# Clock_Distribution.net
KiCad netlist of a schematic drawn in Altium Designer
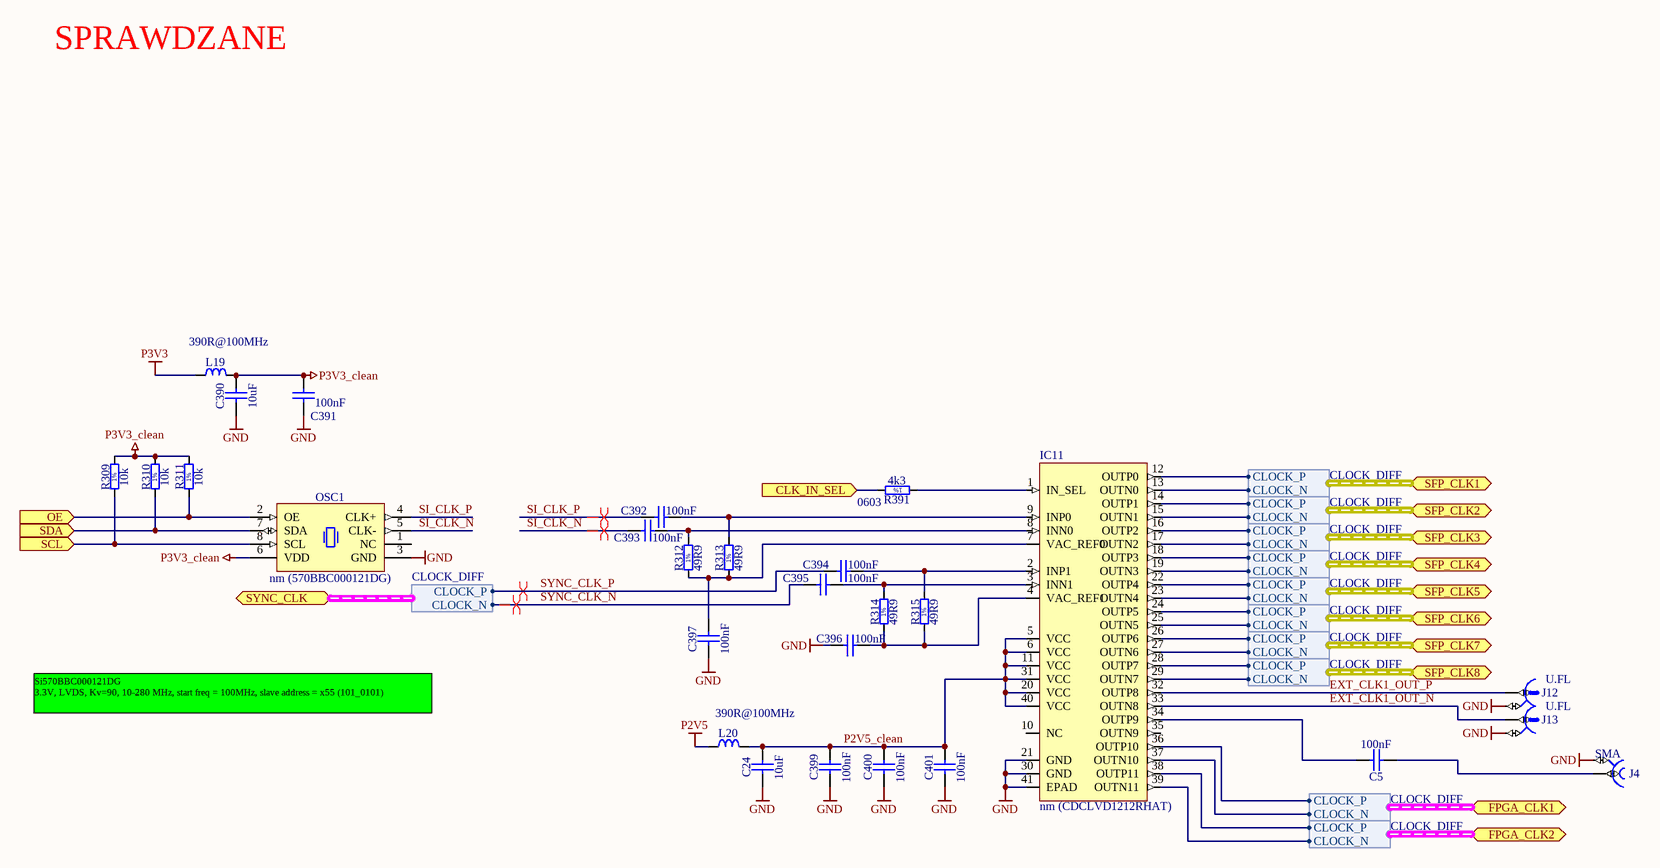
[diagram p0: Clock_Distribution.SchDoc]

(export (version "E")
  (design (tool "Eeschema 10.0.6"))
  (components
    (comp (ref "C5")
      (value "100nF")
      (footprint "CAPC1005X55N")
      (description "Non-polarised capacitor")
      (fields
        (field (name "PART NUMBER") "CC0402_100NF_16V_10%_X7R")
        (field (name "VOLTAGE") "16V")
        (field (name "AUTHOR") "CERN DEM JLC")
      )
      (libsource (lib "Capacitors") (part "Capacitor - non polarized"))
    )
    (comp (ref "C24")
      (value "10uF")
      (footprint "CAPC2012X135N")
      (description "Non-polarised capacitor")
      (fields
        (field (name "PART NUMBER") "CC0805_10UF_10V_10%_X7R")
        (field (name "VOLTAGE") "10V")
        (field (name "AUTHOR") "CERN DEM JLC")
      )
      (libsource (lib "Capacitors") (part "Capacitor - non polarized"))
    )
    (comp (ref "C390")
      (value "10uF")
      (footprint "CAPC2012X135N")
      (description "Non-polarised capacitor")
      (fields
        (field (name "PART NUMBER") "CC0805_10UF_10V_10%_X7R")
        (field (name "VOLTAGE") "10V")
        (field (name "AUTHOR") "CERN DEM JLC")
      )
      (libsource (lib "Capacitors") (part "Capacitor - non polarized"))
    )
    (comp (ref "C391")
      (value "100nF")
      (footprint "CAPC0603X33N")
      (description "Non-polarised capacitor")
      (fields
        (field (name "PART NUMBER") "CC0201_100NF_6.3V_10%_X5R")
        (field (name "VOLTAGE") "6.3V")
        (field (name "AUTHOR") "CERN DEM JLC")
      )
      (libsource (lib "Capacitors") (part "Capacitor - non polarized"))
    )
    (comp (ref "C392")
      (value "100nF")
      (footprint "CAPC0603X33N")
      (description "Non-polarised capacitor")
      (fields
        (field (name "PART NUMBER") "CC0201_100NF_6.3V_10%_X5R")
        (field (name "VOLTAGE") "6.3V")
        (field (name "AUTHOR") "CERN DEM JLC")
      )
      (libsource (lib "Capacitors") (part "Capacitor - non polarized"))
    )
    (comp (ref "C393")
      (value "100nF")
      (footprint "CAPC0603X33N")
      (description "Non-polarised capacitor")
      (fields
        (field (name "PART NUMBER") "CC0201_100NF_6.3V_10%_X5R")
        (field (name "VOLTAGE") "6.3V")
        (field (name "AUTHOR") "CERN DEM JLC")
      )
      (libsource (lib "Capacitors") (part "Capacitor - non polarized"))
    )
    (comp (ref "C394")
      (value "100nF")
      (footprint "CAPC0603X33N")
      (description "Non-polarised capacitor")
      (fields
        (field (name "PART NUMBER") "CC0201_100NF_6.3V_10%_X5R")
        (field (name "VOLTAGE") "6.3V")
        (field (name "AUTHOR") "CERN DEM JLC")
      )
      (libsource (lib "Capacitors") (part "Capacitor - non polarized"))
    )
    (comp (ref "C395")
      (value "100nF")
      (footprint "CAPC0603X33N")
      (description "Non-polarised capacitor")
      (fields
        (field (name "PART NUMBER") "CC0201_100NF_6.3V_10%_X5R")
        (field (name "VOLTAGE") "6.3V")
        (field (name "AUTHOR") "CERN DEM JLC")
      )
      (libsource (lib "Capacitors") (part "Capacitor - non polarized"))
    )
    (comp (ref "C396")
      (value "100nF")
      (footprint "CAPC0603X33N")
      (description "Non-polarised capacitor")
      (fields
        (field (name "PART NUMBER") "CC0201_100NF_6.3V_10%_X5R")
        (field (name "VOLTAGE") "6.3V")
        (field (name "AUTHOR") "CERN DEM JLC")
      )
      (libsource (lib "Capacitors") (part "Capacitor - non polarized"))
    )
    (comp (ref "C397")
      (value "100nF")
      (footprint "CAPC0603X33N")
      (description "Non-polarised capacitor")
      (fields
        (field (name "PART NUMBER") "CC0201_100NF_6.3V_10%_X5R")
        (field (name "VOLTAGE") "6.3V")
        (field (name "AUTHOR") "CERN DEM JLC")
      )
      (libsource (lib "Capacitors") (part "Capacitor - non polarized"))
    )
    (comp (ref "C399")
      (value "100nF")
      (footprint "CAPC0603X33N")
      (description "Non-polarised capacitor")
      (fields
        (field (name "PART NUMBER") "CC0201_100NF_6.3V_10%_X5R")
        (field (name "VOLTAGE") "6.3V")
        (field (name "AUTHOR") "CERN DEM JLC")
      )
      (libsource (lib "Capacitors") (part "Capacitor - non polarized"))
    )
    (comp (ref "C400")
      (value "100nF")
      (footprint "CAPC0603X33N")
      (description "Non-polarised capacitor")
      (fields
        (field (name "PART NUMBER") "CC0201_100NF_6.3V_10%_X5R")
        (field (name "VOLTAGE") "6.3V")
        (field (name "AUTHOR") "CERN DEM JLC")
      )
      (libsource (lib "Capacitors") (part "Capacitor - non polarized"))
    )
    (comp (ref "C401")
      (value "100nF")
      (footprint "CAPC0603X33N")
      (description "Non-polarised capacitor")
      (fields
        (field (name "PART NUMBER") "CC0201_100NF_6.3V_10%_X5R")
        (field (name "VOLTAGE") "6.3V")
        (field (name "AUTHOR") "CERN DEM JLC")
      )
      (libsource (lib "Capacitors") (part "Capacitor - non polarized"))
    )
    (comp (ref "IC11")
      (value "nm (CDCLVD1212RHAT)")
      (footprint "QFN50P600-40")
      (description "Low Jitter, 2-Input Selectable 1:12 Universal-to-LVDS Buffer")
      (libsource (lib "LIBRARY_SCH") (part "CLOCK_CDCLVD1212"))
    )
    (comp (ref "J4")
      (value "SMA")
      (footprint "HUBER-SUHNER_85 SMA-50-0-101/111 NE")
      (fields
        (field (name "PART NUMBER") "HUBER-SUHNER_85_SMA-50-0-101/111_NE")
        (field (name "MANUFACTURER") "HUBER+SUHNER")
        (field (name "MANUFACTURER PART NUMBER") "85_SMA-50-0-101/111_NE")
        (field (name "AUTHOR") "CERN DEM JLC")
      )
      (libsource (lib "Connectors") (part "Coax_1Female_1Shield"))
    )
    (comp (ref "J12")
      (value "U.FL")
      (footprint "HIROSE_U.FL-R-SMT-1(10)")
      (fields
        (field (name "PART NUMBER") "HIROSE_U.FL-R-SMT-1(10)")
        (field (name "MANUFACTURER") "HIROSE (HRS)")
        (field (name "MANUFACTURER PART NUMBER") "U.FL-R-SMT-1(10)")
        (field (name "AUTHOR") "CERN DEM JLC")
      )
      (libsource (lib "Connectors") (part "Coax_1Male_1Shield"))
    )
    (comp (ref "J13")
      (value "U.FL")
      (footprint "HIROSE_U.FL-R-SMT-1(10)")
      (fields
        (field (name "PART NUMBER") "HIROSE_U.FL-R-SMT-1(10)")
        (field (name "MANUFACTURER") "HIROSE (HRS)")
        (field (name "MANUFACTURER PART NUMBER") "U.FL-R-SMT-1(10)")
        (field (name "AUTHOR") "CERN DEM JLC")
      )
      (libsource (lib "Connectors") (part "Coax_1Male_1Shield"))
    )
    (comp (ref "L19")
      (value "390R@100MHz")
      (footprint "INDC1608X95N")
      (description "Inductor")
      (fields
        (field (name "PART NUMBER") "IND0603_TDK_MPZ1608R391A")
        (field (name "POWER") "1.2A")
        (field (name "AUTHOR") "CERN DEM JLC")
      )
      (libsource (lib "Inductors & Transformers") (part "Inductor"))
    )
    (comp (ref "L20")
      (value "390R@100MHz")
      (footprint "INDC1608X95N")
      (description "Inductor")
      (fields
        (field (name "PART NUMBER") "IND0603_TDK_MPZ1608R391A")
        (field (name "POWER") "1.2A")
        (field (name "AUTHOR") "CERN DEM JLC")
      )
      (libsource (lib "Inductors & Transformers") (part "Inductor"))
    )
    (comp (ref "OSC1")
      (value "nm (570BBC000121DG)")
      (footprint "OSC_SILICON-LAB_SI570")
      (description "Any-Rate I2C Programmable XO Oscillator Si570 Serie")
      (fields
        (field (name "PART NUMBER") "OSC_10-280MHZ_SILICON-LAB_Si570BBC000121DG")
        (field (name "MANUFACTURER") "SILICON LABS")
        (field (name "AUTHOR") "CERN DEM JLC")
      )
      (libsource (lib "ICs And Semiconductors") (part "Oscillator SILICON-LAB_Si570"))
    )
    (comp (ref "R309")
      (value "10k")
      (footprint "RESC1005X40N")
      (description "Resistor - 1%")
      (fields
        (field (name "PART NUMBER") "R0402_10K_1%_0.0625W_100PPM")
        (field (name "POWER") "0.0625W")
        (field (name "AUTHOR") "CERN DEM JLC")
      )
      (libsource (lib "Resistors") (part "Resistor - 1%"))
    )
    (comp (ref "R310")
      (value "10k")
      (footprint "RESC1005X40N")
      (description "Resistor - 1%")
      (fields
        (field (name "PART NUMBER") "R0402_10K_1%_0.0625W_100PPM")
        (field (name "POWER") "0.0625W")
        (field (name "AUTHOR") "CERN DEM JLC")
      )
      (libsource (lib "Resistors") (part "Resistor - 1%"))
    )
    (comp (ref "R311")
      (value "10k")
      (footprint "RESC1005X40N")
      (description "Resistor - 1%")
      (fields
        (field (name "PART NUMBER") "R0402_10K_1%_0.0625W_100PPM")
        (field (name "POWER") "0.0625W")
        (field (name "AUTHOR") "CERN DEM JLC")
      )
      (libsource (lib "Resistors") (part "Resistor - 1%"))
    )
    (comp (ref "R312")
      (value "49R9")
      (footprint "RESC1005X40N")
      (description "Resistor - 1%")
      (fields
        (field (name "PART NUMBER") "R0402_49R9_1%_0.0625W_100PPM")
        (field (name "POWER") "0.0625W")
        (field (name "AUTHOR") "CERN DEM JLC")
      )
      (libsource (lib "Resistors") (part "Resistor - 1%"))
    )
    (comp (ref "R313")
      (value "49R9")
      (footprint "RESC1005X40N")
      (description "Resistor - 1%")
      (fields
        (field (name "PART NUMBER") "R0402_49R9_1%_0.0625W_100PPM")
        (field (name "POWER") "0.0625W")
        (field (name "AUTHOR") "CERN DEM JLC")
      )
      (libsource (lib "Resistors") (part "Resistor - 1%"))
    )
    (comp (ref "R314")
      (value "49R9")
      (footprint "RESC1005X40N")
      (description "Resistor - 1%")
      (fields
        (field (name "PART NUMBER") "R0402_49R9_1%_0.0625W_100PPM")
        (field (name "POWER") "0.0625W")
        (field (name "AUTHOR") "CERN DEM JLC")
      )
      (libsource (lib "Resistors") (part "Resistor - 1%"))
    )
    (comp (ref "R315")
      (value "49R9")
      (footprint "RESC1005X40N")
      (description "Resistor - 1%")
      (fields
        (field (name "PART NUMBER") "R0402_49R9_1%_0.0625W_100PPM")
        (field (name "POWER") "0.0625W")
        (field (name "AUTHOR") "CERN DEM JLC")
      )
      (libsource (lib "Resistors") (part "Resistor - 1%"))
    )
    (comp (ref "R391")
      (value "4k3")
      (footprint "RESC1608X55N")
      (description "Resistor - 1%")
      (fields
        (field (name "PART NUMBER") "R0603_4K3_1%_0.1W_100PPM")
        (field (name "POWER") "0.1W")
        (field (name "CASE") "0603")
        (field (name "AUTHOR") "CERN DEM JLC")
      )
      (libsource (lib "Resistors") (part "Resistor - 1%"))
    )
  )
  (nets
    (net (code "3") (name "/CLK_IN_SEL") (class "Default")
      (node (ref "R391") (pin "2") (pinfunction "2_2") (pintype "passive"))
    )
    (net (code "4") (name "/EXT_CLK1_OUT_N") (class "Default")
      (node (ref "IC11") (pin "33") (pinfunction "OUTN8_33") (pintype "output"))
      (node (ref "J13") (pin "1") (pinfunction "1_1") (pintype "bidirectional"))
    )
    (net (code "5") (name "/EXT_CLK1_OUT_P") (class "Default")
      (node (ref "IC11") (pin "32") (pinfunction "OUTP8_32") (pintype "output"))
      (node (ref "J12") (pin "1") (pinfunction "1_1") (pintype "bidirectional"))
    )
    (net (code "6") (name "/OE") (class "Default")
      (node (ref "OSC1") (pin "2") (pinfunction "OE_2") (pintype "input"))
      (node (ref "R311") (pin "1") (pinfunction "1_1") (pintype "passive"))
    )
    (net (code "7") (name "/P2V5_clean") (class "Default")
      (node (ref "C24") (pin "2") (pinfunction "2_2") (pintype "passive"))
      (node (ref "C399") (pin "2") (pinfunction "2_2") (pintype "passive"))
      (node (ref "C400") (pin "2") (pinfunction "2_2") (pintype "passive"))
      (node (ref "C401") (pin "2") (pinfunction "2_2") (pintype "passive"))
      (node (ref "IC11") (pin "11") (pinfunction "VCC_11") (pintype "power_in"))
      (node (ref "IC11") (pin "20") (pinfunction "VCC_20") (pintype "power_in"))
      (node (ref "IC11") (pin "31") (pinfunction "VCC_31") (pintype "power_in"))
      (node (ref "IC11") (pin "40") (pinfunction "VCC_40") (pintype "power_in"))
      (node (ref "IC11") (pin "5") (pinfunction "VCC_5") (pintype "power_in"))
      (node (ref "IC11") (pin "6") (pinfunction "VCC_6") (pintype "power_in"))
      (node (ref "L20") (pin "2") (pinfunction "2_2") (pintype "passive"))
    )
    (net (code "8") (name "/SCL") (class "Default")
      (node (ref "OSC1") (pin "8") (pinfunction "SCL_8") (pintype "input"))
      (node (ref "R309") (pin "1") (pinfunction "1_1") (pintype "passive"))
    )
    (net (code "9") (name "/SDA") (class "Default")
      (node (ref "OSC1") (pin "7") (pinfunction "SDA_7") (pintype "bidirectional"))
      (node (ref "R310") (pin "1") (pinfunction "1_1") (pintype "passive"))
    )
    (net (code "11") (name "/SI_CLK_N") (class "Default")
      (node (ref "C393") (pin "2") (pinfunction "2_2") (pintype "passive"))
      (node (ref "OSC1") (pin "5") (pinfunction "CLK-_5") (pintype "output"))
    )
    (net (code "12") (name "/SI_CLK_P") (class "Default")
      (node (ref "C392") (pin "2") (pinfunction "2_2") (pintype "passive"))
      (node (ref "OSC1") (pin "4") (pinfunction "CLK+_4") (pintype "output"))
    )
    (net (code "13") (name "/SYNC_CLK_N") (class "Default")
      (node (ref "C395") (pin "2") (pinfunction "2_2") (pintype "passive"))
    )
    (net (code "14") (name "/SYNC_CLK_P") (class "Default")
      (node (ref "C394") (pin "2") (pinfunction "2_2") (pintype "passive"))
    )
    (net (code "16") (name "GND") (class "Default")
      (node (ref "C24") (pin "1") (pinfunction "1_1") (pintype "passive"))
      (node (ref "C390") (pin "1") (pinfunction "1_1") (pintype "passive"))
      (node (ref "C391") (pin "1") (pinfunction "1_1") (pintype "passive"))
      (node (ref "C396") (pin "1") (pinfunction "1_1") (pintype "passive"))
      (node (ref "C397") (pin "1") (pinfunction "1_1") (pintype "passive"))
      (node (ref "C399") (pin "1") (pinfunction "1_1") (pintype "passive"))
      (node (ref "C400") (pin "1") (pinfunction "1_1") (pintype "passive"))
      (node (ref "C401") (pin "1") (pinfunction "1_1") (pintype "passive"))
      (node (ref "IC11") (pin "21") (pinfunction "GND_21") (pintype "power_in"))
      (node (ref "IC11") (pin "30") (pinfunction "GND_30") (pintype "power_in"))
      (node (ref "IC11") (pin "41") (pinfunction "EPAD_41") (pintype "power_in"))
      (node (ref "J12") (pin "2") (pinfunction "2_2") (pintype "bidirectional"))
      (node (ref "J13") (pin "2") (pinfunction "2_2") (pintype "bidirectional"))
      (node (ref "J4") (pin "2") (pinfunction "2_2") (pintype "bidirectional"))
      (node (ref "OSC1") (pin "3") (pinfunction "GND_3") (pintype "power_in"))
    )
    (net (code "17") (name "Net-(C5-Pad2)") (class "Default")
      (node (ref "C5") (pin "2") (pinfunction "2_2") (pintype "passive"))
      (node (ref "J4") (pin "1") (pinfunction "1_1") (pintype "bidirectional"))
    )
    (net (code "18") (name "Net-(IC11-INN0)") (class "Default")
      (node (ref "C393") (pin "1") (pinfunction "1_1") (pintype "passive"))
      (node (ref "IC11") (pin "8") (pinfunction "INN0_8") (pintype "input"))
      (node (ref "R312") (pin "2") (pinfunction "2_2") (pintype "passive"))
    )
    (net (code "19") (name "Net-(IC11-INN1)") (class "Default")
      (node (ref "C395") (pin "1") (pinfunction "1_1") (pintype "passive"))
      (node (ref "IC11") (pin "3") (pinfunction "INN1_3") (pintype "input"))
      (node (ref "R314") (pin "2") (pinfunction "2_2") (pintype "passive"))
    )
    (net (code "20") (name "Net-(IC11-INP0)") (class "Default")
      (node (ref "C392") (pin "1") (pinfunction "1_1") (pintype "passive"))
      (node (ref "IC11") (pin "9") (pinfunction "INP0_9") (pintype "input"))
      (node (ref "R313") (pin "2") (pinfunction "2_2") (pintype "passive"))
    )
    (net (code "21") (name "Net-(IC11-INP1)") (class "Default")
      (node (ref "C394") (pin "1") (pinfunction "1_1") (pintype "passive"))
      (node (ref "IC11") (pin "2") (pinfunction "INP1_2") (pintype "input"))
      (node (ref "R315") (pin "2") (pinfunction "2_2") (pintype "passive"))
    )
    (net (code "22") (name "Net-(IC11-IN_SEL)") (class "Default")
      (node (ref "IC11") (pin "1") (pinfunction "IN_SEL_1") (pintype "input"))
      (node (ref "R391") (pin "1") (pinfunction "1_1") (pintype "passive"))
    )
    (net (code "23") (name "Net-(IC11-OUTP9)") (class "Default")
      (node (ref "C5") (pin "1") (pinfunction "1_1") (pintype "passive"))
      (node (ref "IC11") (pin "34") (pinfunction "OUTP9_34") (pintype "output"))
    )
    (net (code "24") (name "Net-(IC11-VAC_REF0)") (class "Default")
      (node (ref "C397") (pin "2") (pinfunction "2_2") (pintype "passive"))
      (node (ref "IC11") (pin "7") (pinfunction "VAC_REF0_7") (pintype "power_in"))
      (node (ref "R312") (pin "1") (pinfunction "1_1") (pintype "passive"))
      (node (ref "R313") (pin "1") (pinfunction "1_1") (pintype "passive"))
    )
    (net (code "25") (name "Net-(IC11-VAC_REF1)") (class "Default")
      (node (ref "C396") (pin "2") (pinfunction "2_2") (pintype "passive"))
      (node (ref "IC11") (pin "4") (pinfunction "VAC_REF1_4") (pintype "power_in"))
      (node (ref "R314") (pin "1") (pinfunction "1_1") (pintype "passive"))
      (node (ref "R315") (pin "1") (pinfunction "1_1") (pintype "passive"))
    )
    (net (code "26") (name "P2V5") (class "Default")
      (node (ref "L20") (pin "1") (pinfunction "1_1") (pintype "passive"))
    )
    (net (code "27") (name "P3V3") (class "Default")
      (node (ref "L19") (pin "1") (pinfunction "1_1") (pintype "passive"))
    )
    (net (code "28") (name "P3V3_clean") (class "Default")
      (node (ref "C390") (pin "2") (pinfunction "2_2") (pintype "passive"))
      (node (ref "C391") (pin "2") (pinfunction "2_2") (pintype "passive"))
      (node (ref "L19") (pin "2") (pinfunction "2_2") (pintype "passive"))
      (node (ref "OSC1") (pin "6") (pinfunction "VDD_6") (pintype "power_in"))
      (node (ref "R309") (pin "2") (pinfunction "2_2") (pintype "passive"))
      (node (ref "R310") (pin "2") (pinfunction "2_2") (pintype "passive"))
      (node (ref "R311") (pin "2") (pinfunction "2_2") (pintype "passive"))
    )
    (net (code "29") (name "unconnected-(IC11-NC-Pad10)") (class "Default")
      (node (ref "IC11") (pin "10") (pinfunction "NC_10") (pintype "passive"))
    )
    (net (code "30") (name "unconnected-(IC11-OUTN0-Pad13)") (class "Default")
      (node (ref "IC11") (pin "13") (pinfunction "OUTN0_13") (pintype "output"))
    )
    (net (code "31") (name "unconnected-(IC11-OUTN1-Pad15)") (class "Default")
      (node (ref "IC11") (pin "15") (pinfunction "OUTN1_15") (pintype "output"))
    )
    (net (code "32") (name "unconnected-(IC11-OUTN2-Pad17)") (class "Default")
      (node (ref "IC11") (pin "17") (pinfunction "OUTN2_17") (pintype "output"))
    )
    (net (code "33") (name "unconnected-(IC11-OUTN3-Pad19)") (class "Default")
      (node (ref "IC11") (pin "19") (pinfunction "OUTN3_19") (pintype "output"))
    )
    (net (code "34") (name "unconnected-(IC11-OUTN4-Pad23)") (class "Default")
      (node (ref "IC11") (pin "23") (pinfunction "OUTN4_23") (pintype "output"))
    )
    (net (code "35") (name "unconnected-(IC11-OUTN5-Pad25)") (class "Default")
      (node (ref "IC11") (pin "25") (pinfunction "OUTN5_25") (pintype "output"))
    )
    (net (code "36") (name "unconnected-(IC11-OUTN6-Pad27)") (class "Default")
      (node (ref "IC11") (pin "27") (pinfunction "OUTN6_27") (pintype "output"))
    )
    (net (code "37") (name "unconnected-(IC11-OUTN7-Pad29)") (class "Default")
      (node (ref "IC11") (pin "29") (pinfunction "OUTN7_29") (pintype "output"))
    )
    (net (code "38") (name "unconnected-(IC11-OUTN9-Pad35)") (class "Default")
      (node (ref "IC11") (pin "35") (pinfunction "OUTN9_35") (pintype "output"))
    )
    (net (code "39") (name "unconnected-(IC11-OUTN10-Pad37)") (class "Default")
      (node (ref "IC11") (pin "37") (pinfunction "OUTN10_37") (pintype "output"))
    )
    (net (code "40") (name "unconnected-(IC11-OUTN11-Pad39)") (class "Default")
      (node (ref "IC11") (pin "39") (pinfunction "OUTN11_39") (pintype "output"))
    )
    (net (code "41") (name "unconnected-(IC11-OUTP0-Pad12)") (class "Default")
      (node (ref "IC11") (pin "12") (pinfunction "OUTP0_12") (pintype "output"))
    )
    (net (code "42") (name "unconnected-(IC11-OUTP1-Pad14)") (class "Default")
      (node (ref "IC11") (pin "14") (pinfunction "OUTP1_14") (pintype "output"))
    )
    (net (code "43") (name "unconnected-(IC11-OUTP2-Pad16)") (class "Default")
      (node (ref "IC11") (pin "16") (pinfunction "OUTP2_16") (pintype "output"))
    )
    (net (code "44") (name "unconnected-(IC11-OUTP3-Pad18)") (class "Default")
      (node (ref "IC11") (pin "18") (pinfunction "OUTP3_18") (pintype "output"))
    )
    (net (code "45") (name "unconnected-(IC11-OUTP4-Pad22)") (class "Default")
      (node (ref "IC11") (pin "22") (pinfunction "OUTP4_22") (pintype "output"))
    )
    (net (code "46") (name "unconnected-(IC11-OUTP5-Pad24)") (class "Default")
      (node (ref "IC11") (pin "24") (pinfunction "OUTP5_24") (pintype "output"))
    )
    (net (code "47") (name "unconnected-(IC11-OUTP6-Pad26)") (class "Default")
      (node (ref "IC11") (pin "26") (pinfunction "OUTP6_26") (pintype "output"))
    )
    (net (code "48") (name "unconnected-(IC11-OUTP7-Pad28)") (class "Default")
      (node (ref "IC11") (pin "28") (pinfunction "OUTP7_28") (pintype "output"))
    )
    (net (code "49") (name "unconnected-(IC11-OUTP10-Pad36)") (class "Default")
      (node (ref "IC11") (pin "36") (pinfunction "OUTP10_36") (pintype "output"))
    )
    (net (code "50") (name "unconnected-(IC11-OUTP11-Pad38)") (class "Default")
      (node (ref "IC11") (pin "38") (pinfunction "OUTP11_38") (pintype "output"))
    )
    (net (code "51") (name "unconnected-(OSC1-NC-Pad1)") (class "Default")
      (node (ref "OSC1") (pin "1") (pinfunction "NC_1") (pintype "passive"))
    )
  )
)
